# SoundSystem_V0_0_1.net
KiCad netlist of a schematic drawn in EasyEDA
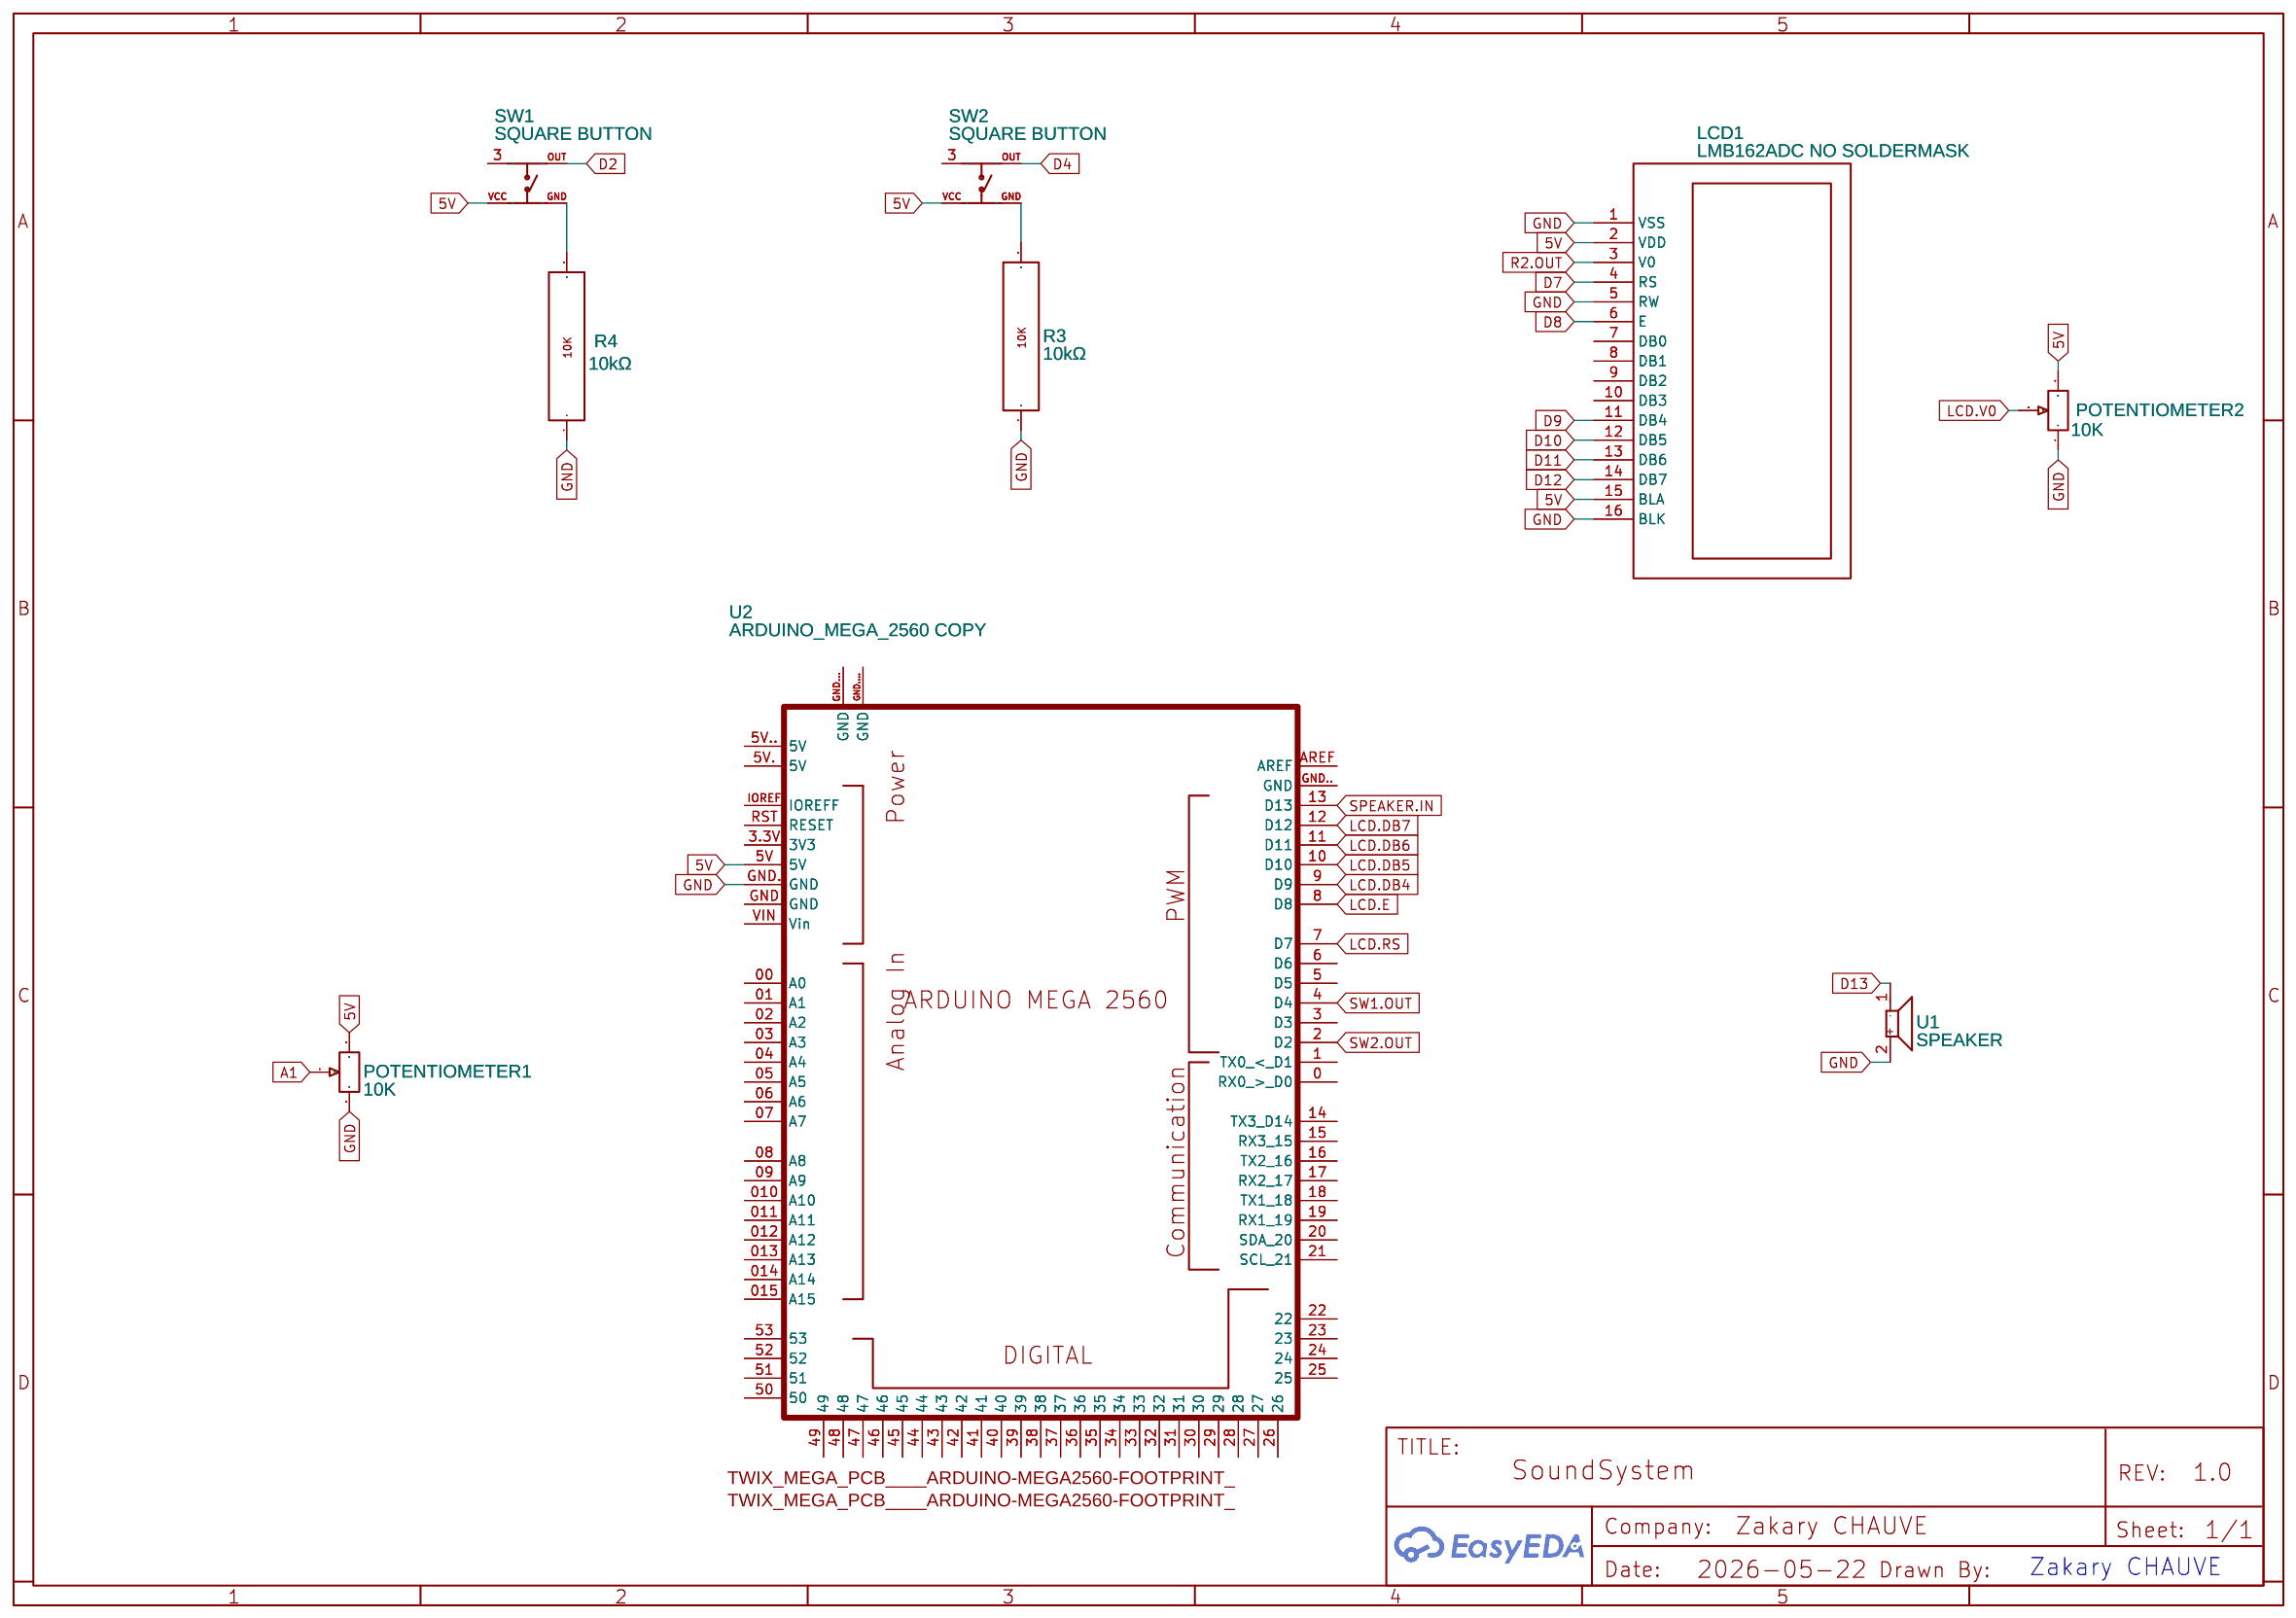
[diagram p0: schematic sheet]

(export (version "E")
  (design (tool "Eeschema 10.0.6"))
  (components
    (comp (ref "LCD1")
      (value "LMB162ADC NO SOLDERMASK")
      (fields (field (name "Manufacturer Part") "LMB162ADC") (field (name "Manufacturer") "TOPWAY"))
      (libsource (lib "") (part "LMB162ADC NO SOLDERMASK"))
    )
    (comp (ref "POTENTIOMETER1")
      (value "10K")
      (fields
        (field (name "Manufacturer Part") "Potentiometer WH160-1-104")
        (field (name "Manufacturer") "JML")
      )
      (libsource (lib "") (part "Pot-10k-Potentiometer"))
    )
    (comp (ref "POTENTIOMETER2")
      (value "10K")
      (fields
        (field (name "Manufacturer Part") "Potentiometer WH160-1-104")
        (field (name "Manufacturer") "JML")
      )
      (libsource (lib "") (part "Pot-10k-Potentiometer"))
    )
    (comp (ref "R3")
      (value "10kΩ")
      (fields (field (name "Manufacturer Part") "MF1/4W-10KΩ±1% T") (field (name "Manufacturer") "CCO(千志电子)"))
      (libsource (lib "") (part "RESISTOR-1/4W-10K-1-PERCENT C"))
    )
    (comp (ref "R4")
      (value "10kΩ")
      (fields (field (name "Manufacturer Part") "MF1/4W-10KΩ±1% T") (field (name "Manufacturer") "CCO(千志电子)"))
      (libsource (lib "") (part "RESISTOR-1/4W-10K-1-PERCENT C"))
    )
    (comp (ref "SW1")
      (value "SQUARE BUTTON")
      (fields
        (field (name "Manufacturer Part") "HX-6x6x7.3-TP FT square button")
        (field (name "Manufacturer") "hanxia(韩下)")
      )
      (libsource (lib "") (part "HX-6X6X7.3-TP FT SQUARE BUTTON"))
    )
    (comp (ref "SW2")
      (value "SQUARE BUTTON")
      (fields
        (field (name "Manufacturer Part") "HX-6x6x7.3-TP FT square button")
        (field (name "Manufacturer") "hanxia(韩下)")
      )
      (libsource (lib "") (part "HX-6X6X7.3-TP FT SQUARE BUTTON"))
    )
    (comp (ref "U1") (value "SPEAKER") (libsource (lib "") (part "speaker")))
    (comp (ref "U2") (value "ARDUINO_MEGA_2560 COPY") (libsource (lib "") (part "ARDUINO_MEGA_2560 COPY")))
  )
  (nets
    (net (code "1") (name "5V") (class "Default")
      (node (ref "LCD1") (pin "15") (pinfunction "BLA_15") (pintype "unspecified"))
      (node (ref "LCD1") (pin "2") (pinfunction "VDD_2") (pintype "unspecified"))
      (node (ref "POTENTIOMETER1") (pin "3") (pinfunction "3_3") (pintype "input"))
      (node (ref "POTENTIOMETER2") (pin "3") (pinfunction "3_3") (pintype "input"))
      (node (ref "SW1") (pin "VCC") (pinfunction "A_VCC") (pintype "unspecified"))
      (node (ref "SW2") (pin "VCC") (pinfunction "A_VCC") (pintype "unspecified"))
      (node (ref "U2") (pin "5V") (pinfunction "5V_5V") (pintype "unspecified"))
    )
    (net (code "2") (name "A1") (class "Default")
      (node (ref "POTENTIOMETER1") (pin "2") (pinfunction "2_2") (pintype "input"))
    )
    (net (code "3") (name "D2") (class "Default")
      (node (ref "SW1") (pin "OUT") (pinfunction "D_OUT") (pintype "unspecified"))
    )
    (net (code "4") (name "D4") (class "Default")
      (node (ref "SW2") (pin "OUT") (pinfunction "D_OUT") (pintype "unspecified"))
    )
    (net (code "5") (name "D7") (class "Default")
      (node (ref "LCD1") (pin "4") (pinfunction "RS_4") (pintype "unspecified"))
    )
    (net (code "6") (name "D8") (class "Default")
      (node (ref "LCD1") (pin "6") (pinfunction "E_6") (pintype "unspecified"))
    )
    (net (code "7") (name "D9") (class "Default")
      (node (ref "LCD1") (pin "11") (pinfunction "DB4_11") (pintype "unspecified"))
    )
    (net (code "8") (name "D10") (class "Default")
      (node (ref "LCD1") (pin "12") (pinfunction "DB5_12") (pintype "unspecified"))
    )
    (net (code "9") (name "D11") (class "Default")
      (node (ref "LCD1") (pin "13") (pinfunction "DB6_13") (pintype "unspecified"))
    )
    (net (code "10") (name "D12") (class "Default")
      (node (ref "LCD1") (pin "14") (pinfunction "DB7_14") (pintype "unspecified"))
    )
    (net (code "11") (name "D13") (class "Default")
      (node (ref "U1") (pin "1") (pinfunction "-_1") (pintype "unspecified"))
    )
    (net (code "12") (name "GND") (class "Default")
      (node (ref "LCD1") (pin "1") (pinfunction "VSS_1") (pintype "unspecified"))
      (node (ref "LCD1") (pin "16") (pinfunction "BLK_16") (pintype "unspecified"))
      (node (ref "LCD1") (pin "5") (pinfunction "RW_5") (pintype "unspecified"))
      (node (ref "POTENTIOMETER1") (pin "1") (pinfunction "1_1") (pintype "input"))
      (node (ref "POTENTIOMETER2") (pin "1") (pinfunction "1_1") (pintype "input"))
      (node (ref "R3") (pin "1") (pinfunction "1_1") (pintype "unspecified"))
      (node (ref "R4") (pin "1") (pinfunction "1_1") (pintype "unspecified"))
      (node (ref "U1") (pin "2") (pinfunction "+_2") (pintype "unspecified"))
      (node (ref "U2") (pin "GND.") (pinfunction "GND_GND.") (pintype "unspecified"))
    )
    (net (code "13") (name "LCD.DB4") (class "Default")
      (node (ref "U2") (pin "9") (pinfunction "D9_9") (pintype "unspecified"))
    )
    (net (code "14") (name "LCD.DB5") (class "Default")
      (node (ref "U2") (pin "10") (pinfunction "D10_10") (pintype "unspecified"))
    )
    (net (code "15") (name "LCD.DB6") (class "Default")
      (node (ref "U2") (pin "11") (pinfunction "D11_11") (pintype "unspecified"))
    )
    (net (code "16") (name "LCD.DB7") (class "Default")
      (node (ref "U2") (pin "12") (pinfunction "D12_12") (pintype "unspecified"))
    )
    (net (code "17") (name "LCD.E") (class "Default")
      (node (ref "U2") (pin "8") (pinfunction "D8_8") (pintype "unspecified"))
    )
    (net (code "18") (name "LCD.RS") (class "Default")
      (node (ref "U2") (pin "7") (pinfunction "D7_7") (pintype "unspecified"))
    )
    (net (code "19") (name "LCD.V0") (class "Default")
      (node (ref "POTENTIOMETER2") (pin "2") (pinfunction "2_2") (pintype "input"))
    )
    (net (code "20") (name "Net-(SW1-B)") (class "Default")
      (node (ref "R4") (pin "2") (pinfunction "2_2") (pintype "unspecified"))
      (node (ref "SW1") (pin "GND") (pinfunction "B_GND") (pintype "unspecified"))
    )
    (net (code "21") (name "Net-(SW2-B)") (class "Default")
      (node (ref "R3") (pin "2") (pinfunction "2_2") (pintype "unspecified"))
      (node (ref "SW2") (pin "GND") (pinfunction "B_GND") (pintype "unspecified"))
    )
    (net (code "22") (name "R2.OUT") (class "Default")
      (node (ref "LCD1") (pin "3") (pinfunction "V0_3") (pintype "unspecified"))
    )
    (net (code "23") (name "SPEAKER.IN") (class "Default")
      (node (ref "U2") (pin "13") (pinfunction "D13_13") (pintype "unspecified"))
    )
    (net (code "24") (name "SW1.OUT") (class "Default")
      (node (ref "U2") (pin "4") (pinfunction "D4_4") (pintype "unspecified"))
    )
    (net (code "25") (name "SW2.OUT") (class "Default")
      (node (ref "U2") (pin "2") (pinfunction "D2_2") (pintype "unspecified"))
    )
    (net (code "26") (name "unconnected-(LCD1-DB0-Pad7)") (class "Default")
      (node (ref "LCD1") (pin "7") (pinfunction "DB0_7") (pintype "unspecified"))
    )
    (net (code "27") (name "unconnected-(LCD1-DB1-Pad8)") (class "Default")
      (node (ref "LCD1") (pin "8") (pinfunction "DB1_8") (pintype "unspecified"))
    )
    (net (code "28") (name "unconnected-(LCD1-DB2-Pad9)") (class "Default")
      (node (ref "LCD1") (pin "9") (pinfunction "DB2_9") (pintype "unspecified"))
    )
    (net (code "29") (name "unconnected-(LCD1-DB3-Pad10)") (class "Default")
      (node (ref "LCD1") (pin "10") (pinfunction "DB3_10") (pintype "unspecified"))
    )
    (net (code "30") (name "unconnected-(SW1-C-Pad3)") (class "Default")
      (node (ref "SW1") (pin "3") (pinfunction "C_3") (pintype "unspecified"))
    )
    (net (code "31") (name "unconnected-(SW2-C-Pad3)") (class "Default")
      (node (ref "SW2") (pin "3") (pinfunction "C_3") (pintype "unspecified"))
    )
    (net (code "32") (name "unconnected-(U2-3V3-Pad3.3V)") (class "Default")
      (node (ref "U2") (pin "3.3V") (pinfunction "3V3_3.3V") (pintype "unspecified"))
    )
    (net (code "33") (name "unconnected-(U2-5V-Pad5V.)") (class "Default")
      (node (ref "U2") (pin "5V.") (pinfunction "5V_5V.") (pintype "unspecified"))
    )
    (net (code "34") (name "unconnected-(U2-5V-Pad5V..)") (class "Default")
      (node (ref "U2") (pin "5V..") (pinfunction "5V_5V..") (pintype "unspecified"))
    )
    (net (code "35") (name "unconnected-(U2-A0-Pad00)") (class "Default")
      (node (ref "U2") (pin "00") (pinfunction "A0_00") (pintype "unspecified"))
    )
    (net (code "36") (name "unconnected-(U2-A1-Pad01)") (class "Default")
      (node (ref "U2") (pin "01") (pinfunction "A1_01") (pintype "unspecified"))
    )
    (net (code "37") (name "unconnected-(U2-A2-Pad02)") (class "Default")
      (node (ref "U2") (pin "02") (pinfunction "A2_02") (pintype "unspecified"))
    )
    (net (code "38") (name "unconnected-(U2-A3-Pad03)") (class "Default")
      (node (ref "U2") (pin "03") (pinfunction "A3_03") (pintype "unspecified"))
    )
    (net (code "39") (name "unconnected-(U2-A4-Pad04)") (class "Default")
      (node (ref "U2") (pin "04") (pinfunction "A4_04") (pintype "unspecified"))
    )
    (net (code "40") (name "unconnected-(U2-A5-Pad05)") (class "Default")
      (node (ref "U2") (pin "05") (pinfunction "A5_05") (pintype "unspecified"))
    )
    (net (code "41") (name "unconnected-(U2-A6-Pad06)") (class "Default")
      (node (ref "U2") (pin "06") (pinfunction "A6_06") (pintype "unspecified"))
    )
    (net (code "42") (name "unconnected-(U2-A7-Pad07)") (class "Default")
      (node (ref "U2") (pin "07") (pinfunction "A7_07") (pintype "unspecified"))
    )
    (net (code "43") (name "unconnected-(U2-A8-Pad08)") (class "Default")
      (node (ref "U2") (pin "08") (pinfunction "A8_08") (pintype "unspecified"))
    )
    (net (code "44") (name "unconnected-(U2-A9-Pad09)") (class "Default")
      (node (ref "U2") (pin "09") (pinfunction "A9_09") (pintype "unspecified"))
    )
    (net (code "45") (name "unconnected-(U2-A10-Pad010)") (class "Default")
      (node (ref "U2") (pin "010") (pinfunction "A10_010") (pintype "unspecified"))
    )
    (net (code "46") (name "unconnected-(U2-A11-Pad011)") (class "Default")
      (node (ref "U2") (pin "011") (pinfunction "A11_011") (pintype "unspecified"))
    )
    (net (code "47") (name "unconnected-(U2-A12-Pad012)") (class "Default")
      (node (ref "U2") (pin "012") (pinfunction "A12_012") (pintype "unspecified"))
    )
    (net (code "48") (name "unconnected-(U2-A13-Pad013)") (class "Default")
      (node (ref "U2") (pin "013") (pinfunction "A13_013") (pintype "unspecified"))
    )
    (net (code "49") (name "unconnected-(U2-A14-Pad014)") (class "Default")
      (node (ref "U2") (pin "014") (pinfunction "A14_014") (pintype "unspecified"))
    )
    (net (code "50") (name "unconnected-(U2-A15-Pad015)") (class "Default")
      (node (ref "U2") (pin "015") (pinfunction "A15_015") (pintype "unspecified"))
    )
    (net (code "51") (name "unconnected-(U2-D3-Pad3)") (class "Default")
      (node (ref "U2") (pin "3") (pinfunction "D3_3") (pintype "unspecified"))
    )
    (net (code "52") (name "unconnected-(U2-D5-Pad5)") (class "Default")
      (node (ref "U2") (pin "5") (pinfunction "D5_5") (pintype "unspecified"))
    )
    (net (code "53") (name "unconnected-(U2-D6-Pad6)") (class "Default")
      (node (ref "U2") (pin "6") (pinfunction "D6_6") (pintype "unspecified"))
    )
    (net (code "54") (name "unconnected-(U2-GND-PadGND..)") (class "Default")
      (node (ref "U2") (pin "GND..") (pinfunction "GND_GND..") (pintype "unspecified"))
    )
    (net (code "55") (name "unconnected-(U2-GND-PadGND...)") (class "Default")
      (node (ref "U2") (pin "GND...") (pinfunction "GND_GND...") (pintype "unspecified"))
    )
    (net (code "56") (name "unconnected-(U2-GND-PadGND....)") (class "Default")
      (node (ref "U2") (pin "GND....") (pinfunction "GND_GND....") (pintype "unspecified"))
    )
    (net (code "57") (name "unconnected-(U2-IOREFF-PadIOREF)") (class "Default")
      (node (ref "U2") (pin "IOREF") (pinfunction "IOREFF_IOREF") (pintype "unspecified"))
    )
    (net (code "58") (name "unconnected-(U2-Pad22)") (class "Default")
      (node (ref "U2") (pin "22") (pinfunction "22_22") (pintype "unspecified"))
    )
    (net (code "59") (name "unconnected-(U2-Pad23)") (class "Default")
      (node (ref "U2") (pin "23") (pinfunction "23_23") (pintype "unspecified"))
    )
    (net (code "60") (name "unconnected-(U2-Pad24)") (class "Default")
      (node (ref "U2") (pin "24") (pinfunction "24_24") (pintype "unspecified"))
    )
    (net (code "61") (name "unconnected-(U2-Pad25)") (class "Default")
      (node (ref "U2") (pin "25") (pinfunction "25_25") (pintype "unspecified"))
    )
    (net (code "62") (name "unconnected-(U2-Pad26)") (class "Default")
      (node (ref "U2") (pin "26") (pinfunction "26_26") (pintype "unspecified"))
    )
    (net (code "63") (name "unconnected-(U2-Pad27)") (class "Default")
      (node (ref "U2") (pin "27") (pinfunction "27_27") (pintype "unspecified"))
    )
    (net (code "64") (name "unconnected-(U2-Pad28)") (class "Default")
      (node (ref "U2") (pin "28") (pinfunction "28_28") (pintype "unspecified"))
    )
    (net (code "65") (name "unconnected-(U2-Pad29)") (class "Default")
      (node (ref "U2") (pin "29") (pinfunction "29_29") (pintype "unspecified"))
    )
    (net (code "66") (name "unconnected-(U2-Pad30)") (class "Default")
      (node (ref "U2") (pin "30") (pinfunction "30_30") (pintype "unspecified"))
    )
    (net (code "67") (name "unconnected-(U2-Pad31)") (class "Default")
      (node (ref "U2") (pin "31") (pinfunction "31_31") (pintype "unspecified"))
    )
    (net (code "68") (name "unconnected-(U2-Pad32)") (class "Default")
      (node (ref "U2") (pin "32") (pinfunction "32_32") (pintype "unspecified"))
    )
    (net (code "69") (name "unconnected-(U2-Pad33)") (class "Default")
      (node (ref "U2") (pin "33") (pinfunction "33_33") (pintype "unspecified"))
    )
    (net (code "70") (name "unconnected-(U2-Pad34)") (class "Default")
      (node (ref "U2") (pin "34") (pinfunction "34_34") (pintype "unspecified"))
    )
    (net (code "71") (name "unconnected-(U2-Pad35)") (class "Default")
      (node (ref "U2") (pin "35") (pinfunction "35_35") (pintype "unspecified"))
    )
    (net (code "72") (name "unconnected-(U2-Pad36)") (class "Default")
      (node (ref "U2") (pin "36") (pinfunction "36_36") (pintype "unspecified"))
    )
    (net (code "73") (name "unconnected-(U2-Pad37)") (class "Default")
      (node (ref "U2") (pin "37") (pinfunction "37_37") (pintype "unspecified"))
    )
    (net (code "74") (name "unconnected-(U2-Pad38)") (class "Default")
      (node (ref "U2") (pin "38") (pinfunction "38_38") (pintype "unspecified"))
    )
    (net (code "75") (name "unconnected-(U2-Pad39)") (class "Default")
      (node (ref "U2") (pin "39") (pinfunction "39_39") (pintype "unspecified"))
    )
    (net (code "76") (name "unconnected-(U2-Pad40)") (class "Default")
      (node (ref "U2") (pin "40") (pinfunction "40_40") (pintype "unspecified"))
    )
    (net (code "77") (name "unconnected-(U2-Pad41)") (class "Default")
      (node (ref "U2") (pin "41") (pinfunction "41_41") (pintype "unspecified"))
    )
    (net (code "78") (name "unconnected-(U2-Pad42)") (class "Default")
      (node (ref "U2") (pin "42") (pinfunction "42_42") (pintype "unspecified"))
    )
    (net (code "79") (name "unconnected-(U2-Pad43)") (class "Default")
      (node (ref "U2") (pin "43") (pinfunction "43_43") (pintype "unspecified"))
    )
    (net (code "80") (name "unconnected-(U2-Pad44)") (class "Default")
      (node (ref "U2") (pin "44") (pinfunction "44_44") (pintype "unspecified"))
    )
    (net (code "81") (name "unconnected-(U2-Pad45)") (class "Default")
      (node (ref "U2") (pin "45") (pinfunction "45_45") (pintype "unspecified"))
    )
    (net (code "82") (name "unconnected-(U2-Pad46)") (class "Default")
      (node (ref "U2") (pin "46") (pinfunction "46_46") (pintype "unspecified"))
    )
    (net (code "83") (name "unconnected-(U2-Pad47)") (class "Default")
      (node (ref "U2") (pin "47") (pinfunction "47_47") (pintype "unspecified"))
    )
    (net (code "84") (name "unconnected-(U2-Pad48)") (class "Default")
      (node (ref "U2") (pin "48") (pinfunction "48_48") (pintype "unspecified"))
    )
    (net (code "85") (name "unconnected-(U2-Pad49)") (class "Default")
      (node (ref "U2") (pin "49") (pinfunction "49_49") (pintype "unspecified"))
    )
    (net (code "86") (name "unconnected-(U2-Pad50)") (class "Default")
      (node (ref "U2") (pin "50") (pinfunction "50_50") (pintype "unspecified"))
    )
    (net (code "87") (name "unconnected-(U2-Pad51)") (class "Default")
      (node (ref "U2") (pin "51") (pinfunction "51_51") (pintype "unspecified"))
    )
    (net (code "88") (name "unconnected-(U2-Pad52)") (class "Default")
      (node (ref "U2") (pin "52") (pinfunction "52_52") (pintype "unspecified"))
    )
    (net (code "89") (name "unconnected-(U2-Pad53)") (class "Default")
      (node (ref "U2") (pin "53") (pinfunction "53_53") (pintype "unspecified"))
    )
    (net (code "90") (name "unconnected-(U2-PadAREF)") (class "Default")
      (node (ref "U2") (pin "AREF") (pinfunction "AREF_AREF") (pintype "unspecified"))
    )
    (net (code "91") (name "unconnected-(U2-PadGND)") (class "Default")
      (node (ref "U2") (pin "GND") (pinfunction "GND_GND") (pintype "unspecified"))
    )
    (net (code "92") (name "unconnected-(U2-RESET-PadRST)") (class "Default")
      (node (ref "U2") (pin "RST") (pinfunction "RESET_RST") (pintype "unspecified"))
    )
    (net (code "93") (name "unconnected-(U2-RX0_>_D0-Pad0)") (class "Default")
      (node (ref "U2") (pin "0") (pinfunction "RX0_>_D0_0") (pintype "unspecified"))
    )
    (net (code "94") (name "unconnected-(U2-RX1_19-Pad19)") (class "Default")
      (node (ref "U2") (pin "19") (pinfunction "RX1_19_19") (pintype "unspecified"))
    )
    (net (code "95") (name "unconnected-(U2-RX2_17-Pad17)") (class "Default")
      (node (ref "U2") (pin "17") (pinfunction "RX2_17_17") (pintype "unspecified"))
    )
    (net (code "96") (name "unconnected-(U2-RX3_15-Pad15)") (class "Default")
      (node (ref "U2") (pin "15") (pinfunction "RX3_15_15") (pintype "unspecified"))
    )
    (net (code "97") (name "unconnected-(U2-SCL_21-Pad21)") (class "Default")
      (node (ref "U2") (pin "21") (pinfunction "SCL_21_21") (pintype "unspecified"))
    )
    (net (code "98") (name "unconnected-(U2-SDA_20-Pad20)") (class "Default")
      (node (ref "U2") (pin "20") (pinfunction "SDA_20_20") (pintype "unspecified"))
    )
    (net (code "99") (name "unconnected-(U2-TX0_<_D1-Pad1)") (class "Default")
      (node (ref "U2") (pin "1") (pinfunction "TX0_<_D1_1") (pintype "unspecified"))
    )
    (net (code "100") (name "unconnected-(U2-TX1_18-Pad18)") (class "Default")
      (node (ref "U2") (pin "18") (pinfunction "TX1_18_18") (pintype "unspecified"))
    )
    (net (code "101") (name "unconnected-(U2-TX2_16-Pad16)") (class "Default")
      (node (ref "U2") (pin "16") (pinfunction "TX2_16_16") (pintype "unspecified"))
    )
    (net (code "102") (name "unconnected-(U2-TX3_D14-Pad14)") (class "Default")
      (node (ref "U2") (pin "14") (pinfunction "TX3_D14_14") (pintype "unspecified"))
    )
    (net (code "103") (name "unconnected-(U2-Vin-PadVIN)") (class "Default")
      (node (ref "U2") (pin "VIN") (pinfunction "Vin_VIN") (pintype "unspecified"))
    )
  )
)
